# design.net
KiCad netlist of a schematic drawn in EasyEDA Pro
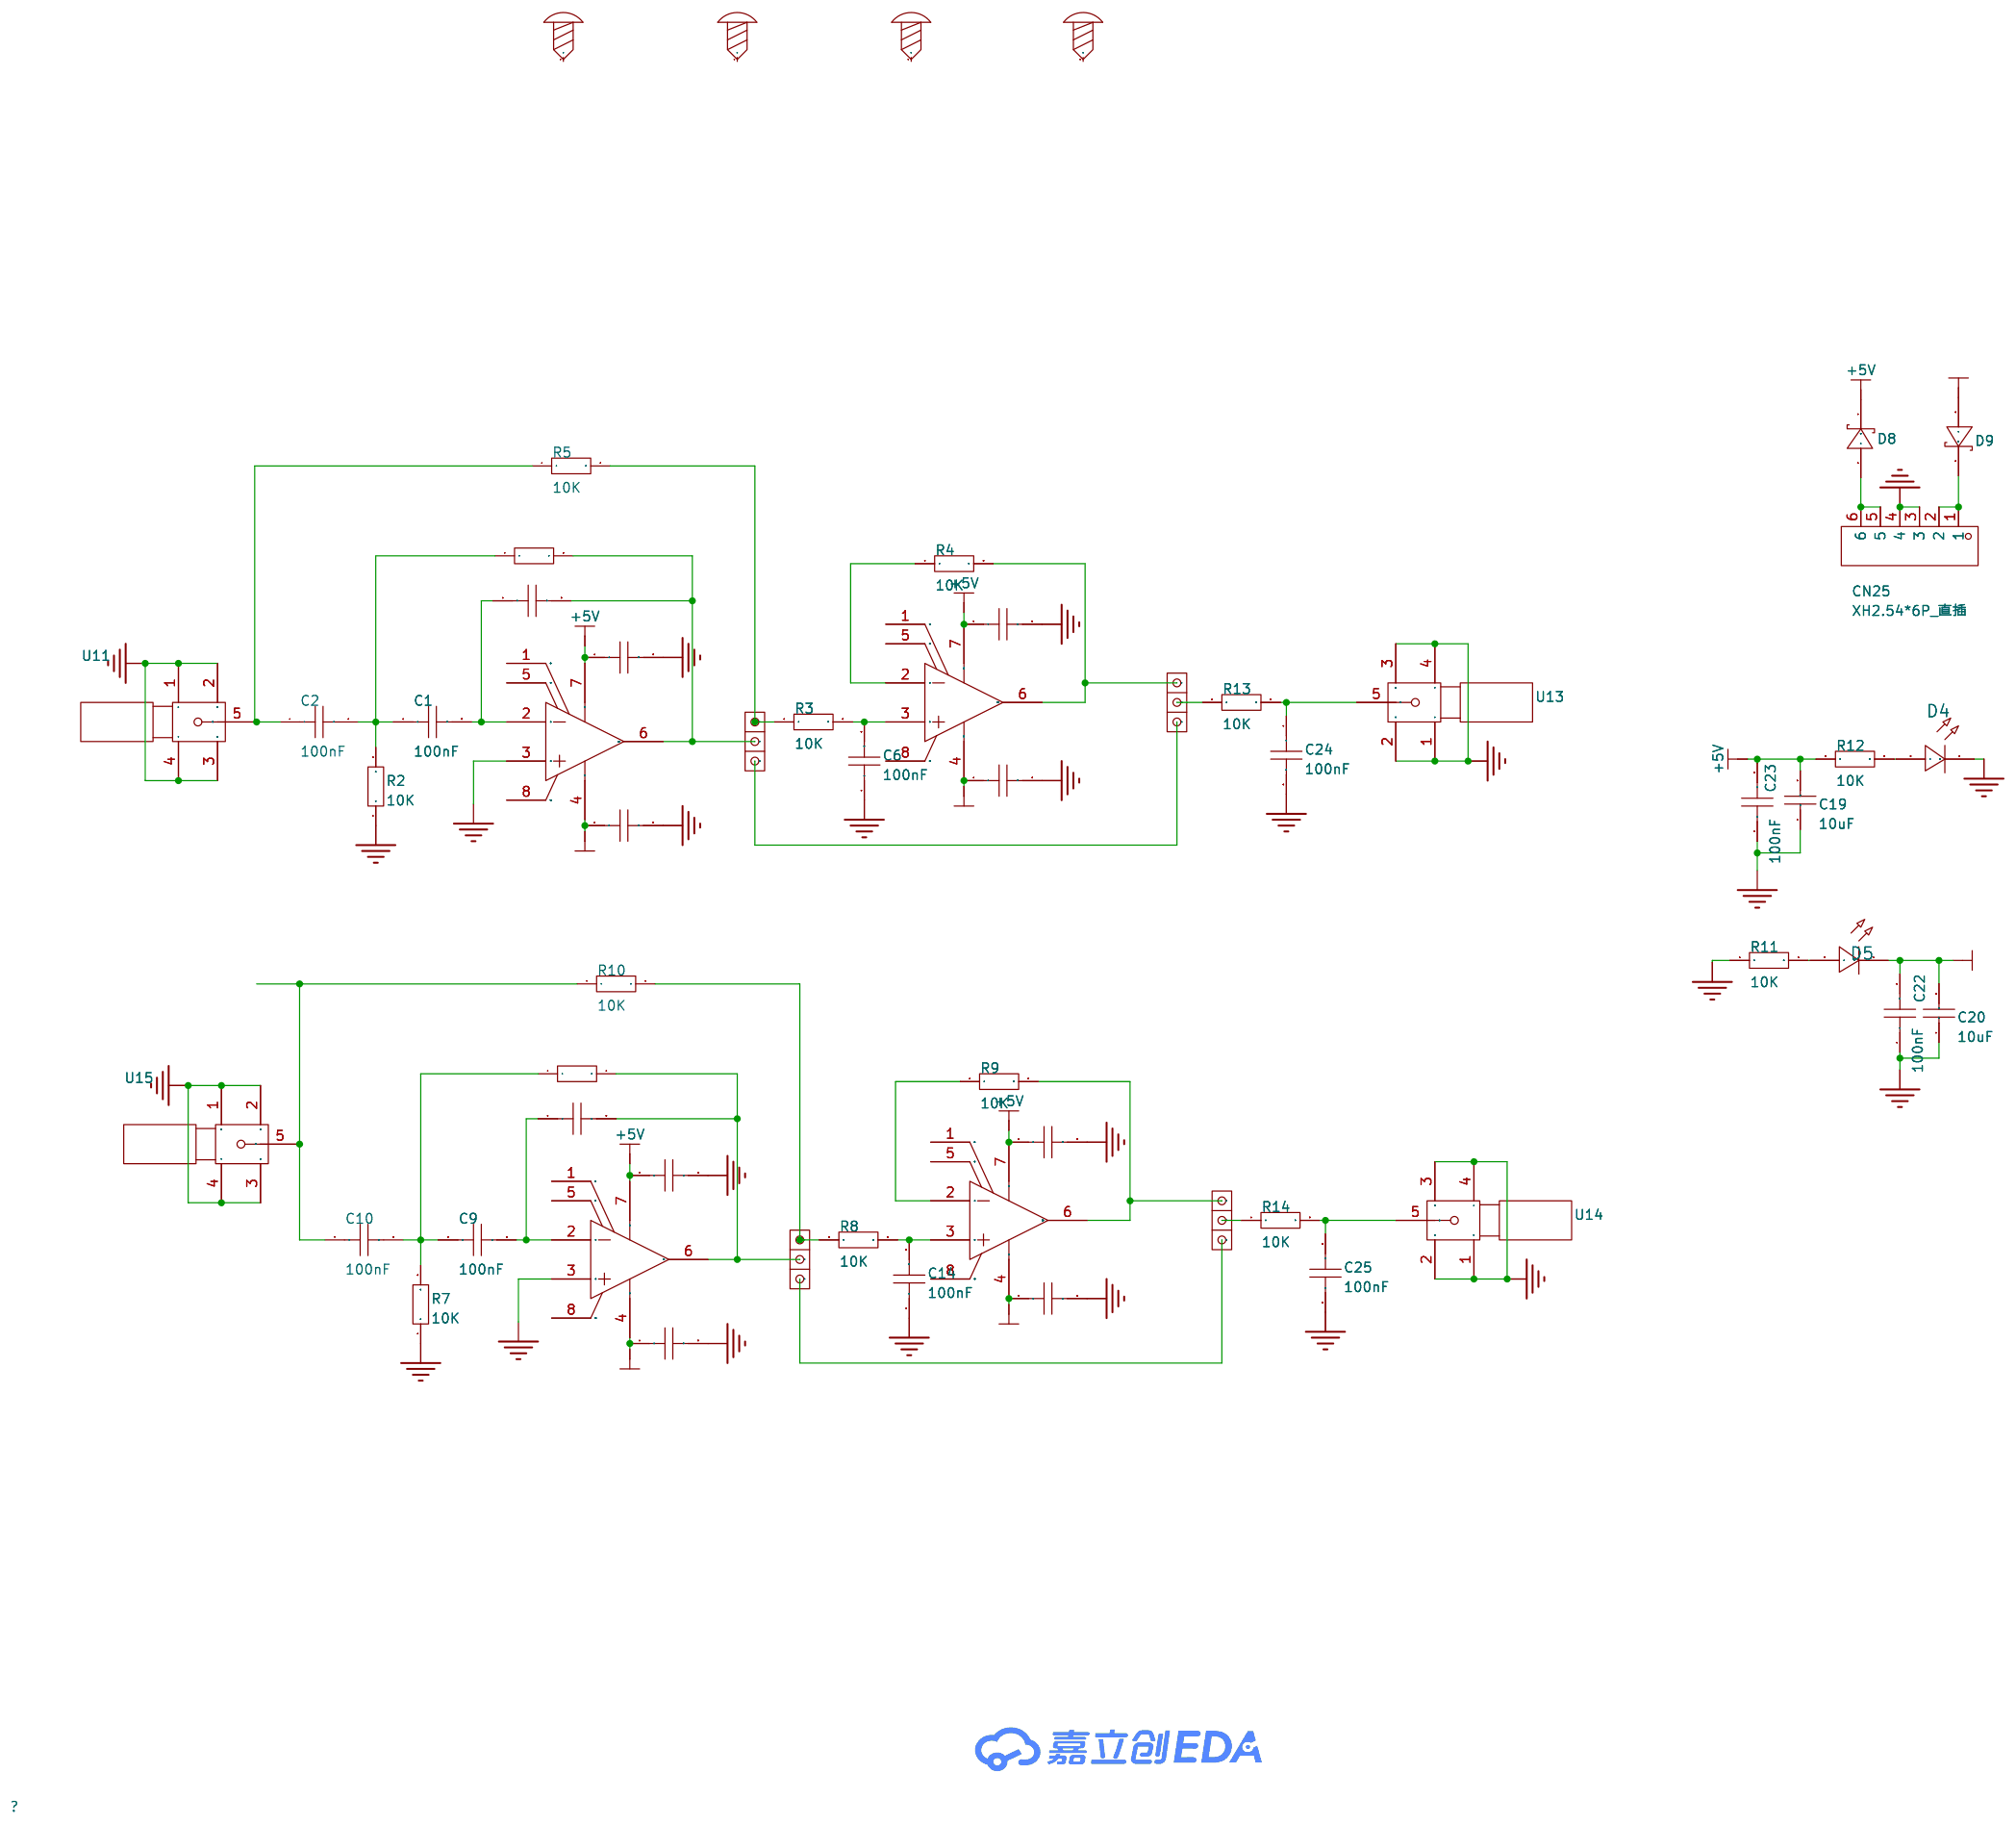
[diagram p0: schematic sheet]

(export (version "E")
  (design (tool "Eeschema 10.0.6"))
  (components
    (comp (ref "C1")
      (value "100nF")
      (footprint "easyedapro:C0805")
      (libsource (lib "easyedapro") (part "CapAcitance"))
    )
    (comp (ref "C2")
      (value "100nF")
      (footprint "easyedapro:C0805")
      (libsource (lib "easyedapro") (part "CapAcitance"))
    )
    (comp (ref "C3")
      (value "100nF")
      (footprint "easyedapro:C0805")
      (libsource (lib "easyedapro") (part "CapAcitance"))
    )
    (comp (ref "C4")
      (value "100nF")
      (footprint "easyedapro:C0805")
      (libsource (lib "easyedapro") (part "CapAcitance"))
    )
    (comp (ref "C5")
      (value "100nF")
      (footprint "easyedapro:C0805")
      (libsource (lib "easyedapro") (part "CapAcitance"))
    )
    (comp (ref "C6")
      (value "100nF")
      (footprint "easyedapro:C0805")
      (libsource (lib "easyedapro") (part "CapAcitance"))
    )
    (comp (ref "C7")
      (value "100nF")
      (footprint "easyedapro:C0805")
      (libsource (lib "easyedapro") (part "CapAcitance"))
    )
    (comp (ref "C8")
      (value "100nF")
      (footprint "easyedapro:C0805")
      (libsource (lib "easyedapro") (part "CapAcitance"))
    )
    (comp (ref "C9")
      (value "100nF")
      (footprint "easyedapro:C0805")
      (libsource (lib "easyedapro") (part "CapAcitance"))
    )
    (comp (ref "C10")
      (value "100nF")
      (footprint "easyedapro:C0805")
      (libsource (lib "easyedapro") (part "CapAcitance"))
    )
    (comp (ref "C11")
      (value "100nF")
      (footprint "easyedapro:C0805")
      (libsource (lib "easyedapro") (part "CapAcitance"))
    )
    (comp (ref "C12")
      (value "100nF")
      (footprint "easyedapro:C0805")
      (libsource (lib "easyedapro") (part "CapAcitance"))
    )
    (comp (ref "C13")
      (value "100nF")
      (footprint "easyedapro:C0805")
      (libsource (lib "easyedapro") (part "CapAcitance"))
    )
    (comp (ref "C14")
      (value "100nF")
      (footprint "easyedapro:C0805")
      (libsource (lib "easyedapro") (part "CapAcitance"))
    )
    (comp (ref "C15")
      (value "100nF")
      (footprint "easyedapro:C0805")
      (libsource (lib "easyedapro") (part "CapAcitance"))
    )
    (comp (ref "C16")
      (value "100nF")
      (footprint "easyedapro:C0805")
      (libsource (lib "easyedapro") (part "CapAcitance"))
    )
    (comp (ref "C19")
      (value "10uF")
      (footprint "easyedapro:C1210")
      (description "容值:10uF;精度:±10%;额定电压:25V;材质(温度系数):X7R;")
      (fields
        (field (name "Manufacturer Part") "CL32B106KAJNNNE")
        (field (name "Manufacturer") "SAMSUNG(三星)")
      )
      (libsource (lib "easyedapro") (part "CL32B106KAJNNNE"))
    )
    (comp (ref "C20")
      (value "10uF")
      (footprint "easyedapro:C1210")
      (description "容值:10uF;精度:±10%;额定电压:25V;材质(温度系数):X7R;")
      (fields
        (field (name "Manufacturer Part") "CL32B106KAJNNNE")
        (field (name "Manufacturer") "SAMSUNG(三星)")
      )
      (libsource (lib "easyedapro") (part "CL32B106KAJNNNE"))
    )
    (comp (ref "C22")
      (value "100nF")
      (footprint "easyedapro:C0805")
      (libsource (lib "easyedapro") (part "CapAcitance"))
    )
    (comp (ref "C23")
      (value "100nF")
      (footprint "easyedapro:C0805")
      (libsource (lib "easyedapro") (part "CapAcitance"))
    )
    (comp (ref "C24")
      (value "100nF")
      (footprint "easyedapro:C0805")
      (libsource (lib "easyedapro") (part "CapAcitance"))
    )
    (comp (ref "C25")
      (value "100nF")
      (footprint "easyedapro:C0805")
      (libsource (lib "easyedapro") (part "CapAcitance"))
    )
    (comp (ref "CN25")
      (value "XH2.54*6P_直插")
      (footprint "easyedapro:CONN-TH_XH2.54-6P")
      (libsource (lib "easyedapro") (part "XH2.54*6P_直插"))
    )
    (comp (ref "D4")
      (value "~")
      (footprint "easyedapro:LED_0805")
      (libsource (lib "easyedapro") (part "LED_R"))
    )
    (comp (ref "D5")
      (value "~")
      (footprint "easyedapro:LED_0805")
      (libsource (lib "easyedapro") (part "LED_R"))
    )
    (comp (ref "D8")
      (value "SD103AWS")
      (footprint "easyedapro:SOD-323_L1.8-W1.3-LS2.5-RD")
      (description "正向压降(Vf):600mV@200mA;直流反向耐压(Vr):40V;整流电流:350mA;")
      (fields (field (name "Manufacturer") "Hottech(合科泰)"))
      (libsource (lib "easyedapro") (part "SD103AWS_C181207"))
    )
    (comp (ref "D9")
      (value "SD103AWS")
      (footprint "easyedapro:SOD-323_L1.8-W1.3-LS2.5-RD")
      (description "正向压降(Vf):600mV@200mA;直流反向耐压(Vr):40V;整流电流:350mA;")
      (fields (field (name "Manufacturer") "Hottech(合科泰)"))
      (libsource (lib "easyedapro") (part "SD103AWS_C181207"))
    )
    (comp (ref "R1") (value "10K") (footprint "easyedapro:R0805") (libsource (lib "easyedapro") (part "电阻")))
    (comp (ref "R2") (value "10K") (footprint "easyedapro:R0805") (libsource (lib "easyedapro") (part "电阻")))
    (comp (ref "R3") (value "10K") (footprint "easyedapro:R0805") (libsource (lib "easyedapro") (part "电阻")))
    (comp (ref "R4") (value "10K") (footprint "easyedapro:R0805") (libsource (lib "easyedapro") (part "电阻")))
    (comp (ref "R5") (value "10K") (footprint "easyedapro:R0805") (libsource (lib "easyedapro") (part "电阻")))
    (comp (ref "R6") (value "10K") (footprint "easyedapro:R0805") (libsource (lib "easyedapro") (part "电阻")))
    (comp (ref "R7") (value "10K") (footprint "easyedapro:R0805") (libsource (lib "easyedapro") (part "电阻")))
    (comp (ref "R8") (value "10K") (footprint "easyedapro:R0805") (libsource (lib "easyedapro") (part "电阻")))
    (comp (ref "R9") (value "10K") (footprint "easyedapro:R0805") (libsource (lib "easyedapro") (part "电阻")))
    (comp (ref "R10") (value "10K") (footprint "easyedapro:R0805") (libsource (lib "easyedapro") (part "电阻")))
    (comp (ref "R11") (value "10K") (footprint "easyedapro:R0805") (libsource (lib "easyedapro") (part "电阻")))
    (comp (ref "R12") (value "10K") (footprint "easyedapro:R0805") (libsource (lib "easyedapro") (part "电阻")))
    (comp (ref "R13") (value "10K") (footprint "easyedapro:R0805") (libsource (lib "easyedapro") (part "电阻")))
    (comp (ref "R14") (value "10K") (footprint "easyedapro:R0805") (libsource (lib "easyedapro") (part "电阻")))
    (comp (ref "SCREW1")
      (value "~")
      (footprint "easyedapro:M3螺丝")
      (libsource (lib "easyedapro") (part "螺丝孔"))
    )
    (comp (ref "SCREW2")
      (value "~")
      (footprint "easyedapro:M3螺丝")
      (libsource (lib "easyedapro") (part "螺丝孔"))
    )
    (comp (ref "SCREW3")
      (value "~")
      (footprint "easyedapro:M3螺丝")
      (libsource (lib "easyedapro") (part "螺丝孔"))
    )
    (comp (ref "SCREW4")
      (value "~")
      (footprint "easyedapro:M3螺丝")
      (libsource (lib "easyedapro") (part "螺丝孔"))
    )
    (comp (ref "U1")
      (value "OPA695IDR")
      (footprint "easyedapro:SOIC-8_L5.0-W4.0-P1.27-LS6.1-BL")
      (description "放大器数:单路;增益带宽积(GBP):-;压摆率(SR):4.3V/ns;输入偏置电流(Ib):20uA;")
      (fields (field (name "Manufacturer") "TI(德州仪器)"))
      (libsource (lib "easyedapro") (part "OPA695IDR"))
    )
    (comp (ref "U2") (value "~") (footprint "easyedapro:1*3跳线") (libsource (lib "easyedapro") (part "1*3跳线")))
    (comp (ref "U3")
      (value "OPA695IDR")
      (footprint "easyedapro:SOIC-8_L5.0-W4.0-P1.27-LS6.1-BL")
      (description "放大器数:单路;增益带宽积(GBP):-;压摆率(SR):4.3V/ns;输入偏置电流(Ib):20uA;")
      (fields (field (name "Manufacturer") "TI(德州仪器)"))
      (libsource (lib "easyedapro") (part "OPA695IDR"))
    )
    (comp (ref "U4") (value "~") (footprint "easyedapro:1*3跳线") (libsource (lib "easyedapro") (part "1*3跳线")))
    (comp (ref "U5")
      (value "OPA695IDR")
      (footprint "easyedapro:SOIC-8_L5.0-W4.0-P1.27-LS6.1-BL")
      (description "放大器数:单路;增益带宽积(GBP):-;压摆率(SR):4.3V/ns;输入偏置电流(Ib):20uA;")
      (fields (field (name "Manufacturer") "TI(德州仪器)"))
      (libsource (lib "easyedapro") (part "OPA695IDR"))
    )
    (comp (ref "U6") (value "~") (footprint "easyedapro:1*3跳线") (libsource (lib "easyedapro") (part "1*3跳线")))
    (comp (ref "U7")
      (value "OPA695IDR")
      (footprint "easyedapro:SOIC-8_L5.0-W4.0-P1.27-LS6.1-BL")
      (description "放大器数:单路;增益带宽积(GBP):-;压摆率(SR):4.3V/ns;输入偏置电流(Ib):20uA;")
      (fields (field (name "Manufacturer") "TI(德州仪器)"))
      (libsource (lib "easyedapro") (part "OPA695IDR"))
    )
    (comp (ref "U8") (value "~") (footprint "easyedapro:1*3跳线") (libsource (lib "easyedapro") (part "1*3跳线")))
    (comp (ref "U11") (value "~") (footprint "easyedapro:SMA") (libsource (lib "easyedapro") (part "SMA")))
    (comp (ref "U13") (value "~") (footprint "easyedapro:SMA") (libsource (lib "easyedapro") (part "SMA")))
    (comp (ref "U14") (value "~") (footprint "easyedapro:SMA") (libsource (lib "easyedapro") (part "SMA")))
    (comp (ref "U15") (value "~") (footprint "easyedapro:SMA") (libsource (lib "easyedapro") (part "SMA")))
  )
  (nets
    (net (code "1") (name "+5V") (class "Default")
      (node (ref "C12") (pin "1") (pinfunction "1_1") (pintype "input"))
      (node (ref "C15") (pin "1") (pinfunction "1_1") (pintype "input"))
      (node (ref "C19") (pin "2") (pinfunction "2_2") (pintype "input"))
      (node (ref "C23") (pin "2") (pinfunction "2_2") (pintype "input"))
      (node (ref "C4") (pin "1") (pinfunction "1_1") (pintype "input"))
      (node (ref "C7") (pin "1") (pinfunction "1_1") (pintype "input"))
      (node (ref "D8") (pin "1") (pinfunction "C_1") (pintype "unspecified"))
      (node (ref "R12") (pin "1") (pinfunction "1_1") (pintype "input"))
      (node (ref "U1") (pin "7") (pinfunction "+VS_7") (pintype "unspecified"))
      (node (ref "U3") (pin "7") (pinfunction "+VS_7") (pintype "unspecified"))
      (node (ref "U5") (pin "7") (pinfunction "+VS_7") (pintype "unspecified"))
      (node (ref "U7") (pin "7") (pinfunction "+VS_7") (pintype "unspecified"))
    )
    (net (code "2") (name "-5V") (class "Default")
      (node (ref "C13") (pin "1") (pinfunction "1_1") (pintype "input"))
      (node (ref "C16") (pin "1") (pinfunction "1_1") (pintype "input"))
      (node (ref "C20") (pin "2") (pinfunction "2_2") (pintype "input"))
      (node (ref "C22") (pin "2") (pinfunction "2_2") (pintype "input"))
      (node (ref "C5") (pin "1") (pinfunction "1_1") (pintype "input"))
      (node (ref "C8") (pin "1") (pinfunction "1_1") (pintype "input"))
      (node (ref "D5") (pin "1") (pinfunction "C_1") (pintype "input"))
      (node (ref "D9") (pin "2") (pinfunction "A_2") (pintype "unspecified"))
      (node (ref "U1") (pin "4") (pinfunction "-VS_4") (pintype "unspecified"))
      (node (ref "U3") (pin "4") (pinfunction "-VS_4") (pintype "unspecified"))
      (node (ref "U5") (pin "4") (pinfunction "-VS_4") (pintype "unspecified"))
      (node (ref "U7") (pin "4") (pinfunction "-VS_4") (pintype "unspecified"))
    )
    (net (code "3") (name "GND") (class "Default")
      (node (ref "C12") (pin "2") (pinfunction "2_2") (pintype "input"))
      (node (ref "C13") (pin "2") (pinfunction "2_2") (pintype "input"))
      (node (ref "C14") (pin "1") (pinfunction "1_1") (pintype "input"))
      (node (ref "C15") (pin "2") (pinfunction "2_2") (pintype "input"))
      (node (ref "C16") (pin "2") (pinfunction "2_2") (pintype "input"))
      (node (ref "C19") (pin "1") (pinfunction "1_1") (pintype "input"))
      (node (ref "C20") (pin "1") (pinfunction "1_1") (pintype "input"))
      (node (ref "C22") (pin "1") (pinfunction "1_1") (pintype "input"))
      (node (ref "C23") (pin "1") (pinfunction "1_1") (pintype "input"))
      (node (ref "C24") (pin "2") (pinfunction "2_2") (pintype "input"))
      (node (ref "C25") (pin "2") (pinfunction "2_2") (pintype "input"))
      (node (ref "C4") (pin "2") (pinfunction "2_2") (pintype "input"))
      (node (ref "C5") (pin "2") (pinfunction "2_2") (pintype "input"))
      (node (ref "C6") (pin "1") (pinfunction "1_1") (pintype "input"))
      (node (ref "C7") (pin "2") (pinfunction "2_2") (pintype "input"))
      (node (ref "C8") (pin "2") (pinfunction "2_2") (pintype "input"))
      (node (ref "CN25") (pin "3") (pinfunction "3_3") (pintype "input"))
      (node (ref "CN25") (pin "4") (pinfunction "4_4") (pintype "input"))
      (node (ref "D4") (pin "1") (pinfunction "C_1") (pintype "input"))
      (node (ref "R11") (pin "1") (pinfunction "1_1") (pintype "input"))
      (node (ref "R2") (pin "1") (pinfunction "1_1") (pintype "input"))
      (node (ref "R7") (pin "1") (pinfunction "1_1") (pintype "input"))
      (node (ref "U1") (pin "3") (pinfunction "+IN_3") (pintype "unspecified"))
      (node (ref "U11") (pin "1") (pinfunction "1_1") (pintype "input"))
      (node (ref "U11") (pin "2") (pinfunction "2_2") (pintype "input"))
      (node (ref "U11") (pin "3") (pinfunction "3_3") (pintype "input"))
      (node (ref "U11") (pin "4") (pinfunction "4_4") (pintype "input"))
      (node (ref "U13") (pin "1") (pinfunction "1_1") (pintype "input"))
      (node (ref "U13") (pin "2") (pinfunction "2_2") (pintype "input"))
      (node (ref "U13") (pin "3") (pinfunction "3_3") (pintype "input"))
      (node (ref "U13") (pin "4") (pinfunction "4_4") (pintype "input"))
      (node (ref "U14") (pin "1") (pinfunction "1_1") (pintype "input"))
      (node (ref "U14") (pin "2") (pinfunction "2_2") (pintype "input"))
      (node (ref "U14") (pin "3") (pinfunction "3_3") (pintype "input"))
      (node (ref "U14") (pin "4") (pinfunction "4_4") (pintype "input"))
      (node (ref "U15") (pin "1") (pinfunction "1_1") (pintype "input"))
      (node (ref "U15") (pin "2") (pinfunction "2_2") (pintype "input"))
      (node (ref "U15") (pin "3") (pinfunction "3_3") (pintype "input"))
      (node (ref "U15") (pin "4") (pinfunction "4_4") (pintype "input"))
      (node (ref "U5") (pin "3") (pinfunction "+IN_3") (pintype "unspecified"))
    )
    (net (code "4") (name "Net-(C1-Pad1)") (class "Default")
      (node (ref "C1") (pin "1") (pinfunction "1_1") (pintype "input"))
      (node (ref "C2") (pin "2") (pinfunction "2_2") (pintype "input"))
      (node (ref "R1") (pin "1") (pinfunction "1_1") (pintype "input"))
      (node (ref "R2") (pin "2") (pinfunction "2_2") (pintype "input"))
    )
    (net (code "5") (name "Net-(C2-Pad1)") (class "Default")
      (node (ref "C2") (pin "1") (pinfunction "1_1") (pintype "input"))
      (node (ref "R5") (pin "1") (pinfunction "1_1") (pintype "input"))
      (node (ref "U11") (pin "5") (pinfunction "5_5") (pintype "input"))
    )
    (net (code "6") (name "Net-(C10-Pad1)") (class "Default")
      (node (ref "C10") (pin "1") (pinfunction "1_1") (pintype "input"))
      (node (ref "R10") (pin "1") (pinfunction "1_1") (pintype "input"))
      (node (ref "U15") (pin "5") (pinfunction "5_5") (pintype "input"))
    )
    (net (code "7") (name "Net-(C10-Pad2)") (class "Default")
      (node (ref "C10") (pin "2") (pinfunction "2_2") (pintype "input"))
      (node (ref "C9") (pin "1") (pinfunction "1_1") (pintype "input"))
      (node (ref "R6") (pin "1") (pinfunction "1_1") (pintype "input"))
      (node (ref "R7") (pin "2") (pinfunction "2_2") (pintype "input"))
    )
    (net (code "8") (name "Net-(C24-Pad1)") (class "Default")
      (node (ref "C24") (pin "1") (pinfunction "1_1") (pintype "input"))
      (node (ref "R13") (pin "2") (pinfunction "2_2") (pintype "input"))
      (node (ref "U13") (pin "5") (pinfunction "5_5") (pintype "input"))
    )
    (net (code "9") (name "Net-(C25-Pad1)") (class "Default")
      (node (ref "C25") (pin "1") (pinfunction "1_1") (pintype "input"))
      (node (ref "R14") (pin "2") (pinfunction "2_2") (pintype "input"))
      (node (ref "U14") (pin "5") (pinfunction "5_5") (pintype "input"))
    )
    (net (code "10") (name "Net-(D4-A)") (class "Default")
      (node (ref "D4") (pin "2") (pinfunction "A_2") (pintype "input"))
      (node (ref "R12") (pin "2") (pinfunction "2_2") (pintype "input"))
    )
    (net (code "11") (name "Net-(D5-A)") (class "Default")
      (node (ref "D5") (pin "2") (pinfunction "A_2") (pintype "input"))
      (node (ref "R11") (pin "2") (pinfunction "2_2") (pintype "input"))
    )
    (net (code "12") (name "Net-(D8-A)") (class "Default")
      (node (ref "CN25") (pin "5") (pinfunction "5_5") (pintype "input"))
      (node (ref "CN25") (pin "6") (pinfunction "6_6") (pintype "input"))
      (node (ref "D8") (pin "2") (pinfunction "A_2") (pintype "unspecified"))
    )
    (net (code "13") (name "Net-(D9-C)") (class "Default")
      (node (ref "CN25") (pin "1") (pinfunction "1_1") (pintype "input"))
      (node (ref "CN25") (pin "2") (pinfunction "2_2") (pintype "input"))
      (node (ref "D9") (pin "1") (pinfunction "C_1") (pintype "unspecified"))
    )
    (net (code "14") (name "Net-(R3-Pad1)") (class "Default")
      (node (ref "R3") (pin "1") (pinfunction "1_1") (pintype "input"))
      (node (ref "R5") (pin "2") (pinfunction "2_2") (pintype "input"))
      (node (ref "U2") (pin "1") (pinfunction "1_1") (pintype "input"))
    )
    (net (code "15") (name "Net-(R10-Pad2)") (class "Default")
      (node (ref "R10") (pin "2") (pinfunction "2_2") (pintype "input"))
      (node (ref "R8") (pin "1") (pinfunction "1_1") (pintype "input"))
      (node (ref "U6") (pin "1") (pinfunction "1_1") (pintype "input"))
    )
    (net (code "16") (name "Net-(R13-Pad1)") (class "Default")
      (node (ref "R13") (pin "1") (pinfunction "1_1") (pintype "input"))
      (node (ref "U4") (pin "2") (pinfunction "2_2") (pintype "input"))
    )
    (net (code "17") (name "Net-(R14-Pad1)") (class "Default")
      (node (ref "R14") (pin "1") (pinfunction "1_1") (pintype "input"))
      (node (ref "U8") (pin "2") (pinfunction "2_2") (pintype "input"))
    )
    (net (code "18") (name "Net-(U1--IN)") (class "Default")
      (node (ref "C1") (pin "2") (pinfunction "2_2") (pintype "input"))
      (node (ref "C3") (pin "1") (pinfunction "1_1") (pintype "input"))
      (node (ref "U1") (pin "2") (pinfunction "-IN_2") (pintype "unspecified"))
    )
    (net (code "19") (name "Net-(U1-Output)") (class "Default")
      (node (ref "C3") (pin "2") (pinfunction "2_2") (pintype "input"))
      (node (ref "R1") (pin "2") (pinfunction "2_2") (pintype "input"))
      (node (ref "U1") (pin "6") (pinfunction "Output_6") (pintype "output"))
      (node (ref "U2") (pin "2") (pinfunction "2_2") (pintype "input"))
    )
    (net (code "20") (name "Net-(U2-Pad3)") (class "Default")
      (node (ref "U2") (pin "3") (pinfunction "3_3") (pintype "input"))
      (node (ref "U4") (pin "3") (pinfunction "3_3") (pintype "input"))
    )
    (net (code "21") (name "Net-(U3-+IN)") (class "Default")
      (node (ref "C6") (pin "2") (pinfunction "2_2") (pintype "input"))
      (node (ref "R3") (pin "2") (pinfunction "2_2") (pintype "input"))
      (node (ref "U3") (pin "3") (pinfunction "+IN_3") (pintype "unspecified"))
    )
    (net (code "22") (name "Net-(U3--IN)") (class "Default")
      (node (ref "R4") (pin "1") (pinfunction "1_1") (pintype "input"))
      (node (ref "U3") (pin "2") (pinfunction "-IN_2") (pintype "unspecified"))
    )
    (net (code "23") (name "Net-(U3-Output)") (class "Default")
      (node (ref "R4") (pin "2") (pinfunction "2_2") (pintype "input"))
      (node (ref "U3") (pin "6") (pinfunction "Output_6") (pintype "output"))
      (node (ref "U4") (pin "1") (pinfunction "1_1") (pintype "input"))
    )
    (net (code "24") (name "Net-(U5--IN)") (class "Default")
      (node (ref "C11") (pin "1") (pinfunction "1_1") (pintype "input"))
      (node (ref "C9") (pin "2") (pinfunction "2_2") (pintype "input"))
      (node (ref "U5") (pin "2") (pinfunction "-IN_2") (pintype "unspecified"))
    )
    (net (code "25") (name "Net-(U5-Output)") (class "Default")
      (node (ref "C11") (pin "2") (pinfunction "2_2") (pintype "input"))
      (node (ref "R6") (pin "2") (pinfunction "2_2") (pintype "input"))
      (node (ref "U5") (pin "6") (pinfunction "Output_6") (pintype "output"))
      (node (ref "U6") (pin "2") (pinfunction "2_2") (pintype "input"))
    )
    (net (code "26") (name "Net-(U6-Pad3)") (class "Default")
      (node (ref "U6") (pin "3") (pinfunction "3_3") (pintype "input"))
      (node (ref "U8") (pin "3") (pinfunction "3_3") (pintype "input"))
    )
    (net (code "27") (name "Net-(U7-+IN)") (class "Default")
      (node (ref "C14") (pin "2") (pinfunction "2_2") (pintype "input"))
      (node (ref "R8") (pin "2") (pinfunction "2_2") (pintype "input"))
      (node (ref "U7") (pin "3") (pinfunction "+IN_3") (pintype "unspecified"))
    )
    (net (code "28") (name "Net-(U7--IN)") (class "Default")
      (node (ref "R9") (pin "1") (pinfunction "1_1") (pintype "input"))
      (node (ref "U7") (pin "2") (pinfunction "-IN_2") (pintype "unspecified"))
    )
    (net (code "29") (name "Net-(U7-Output)") (class "Default")
      (node (ref "R9") (pin "2") (pinfunction "2_2") (pintype "input"))
      (node (ref "U7") (pin "6") (pinfunction "Output_6") (pintype "output"))
      (node (ref "U8") (pin "1") (pinfunction "1_1") (pintype "input"))
    )
    (net (code "30") (name "unconnected-(SCREW1-Pad1)") (class "Default")
      (node (ref "SCREW1") (pin "1") (pinfunction "1_1") (pintype "input"))
    )
    (net (code "31") (name "unconnected-(SCREW2-Pad1)") (class "Default")
      (node (ref "SCREW2") (pin "1") (pinfunction "1_1") (pintype "input"))
    )
    (net (code "32") (name "unconnected-(SCREW3-Pad1)") (class "Default")
      (node (ref "SCREW3") (pin "1") (pinfunction "1_1") (pintype "input"))
    )
    (net (code "33") (name "unconnected-(SCREW4-Pad1)") (class "Default")
      (node (ref "SCREW4") (pin "1") (pinfunction "1_1") (pintype "input"))
    )
    (net (code "34") (name "unconnected-(U1-DIS#-Pad8)") (class "Default")
      (node (ref "U1") (pin "8") (pinfunction "DIS#_8") (pintype "unspecified"))
    )
    (net (code "35") (name "unconnected-(U1-NC-Pad1)") (class "Default")
      (node (ref "U1") (pin "1") (pinfunction "NC_1") (pintype "unspecified"))
    )
    (net (code "36") (name "unconnected-(U1-NC-Pad5)") (class "Default")
      (node (ref "U1") (pin "5") (pinfunction "NC_5") (pintype "unspecified"))
    )
    (net (code "37") (name "unconnected-(U3-DIS#-Pad8)") (class "Default")
      (node (ref "U3") (pin "8") (pinfunction "DIS#_8") (pintype "unspecified"))
    )
    (net (code "38") (name "unconnected-(U3-NC-Pad1)") (class "Default")
      (node (ref "U3") (pin "1") (pinfunction "NC_1") (pintype "unspecified"))
    )
    (net (code "39") (name "unconnected-(U3-NC-Pad5)") (class "Default")
      (node (ref "U3") (pin "5") (pinfunction "NC_5") (pintype "unspecified"))
    )
    (net (code "40") (name "unconnected-(U5-DIS#-Pad8)") (class "Default")
      (node (ref "U5") (pin "8") (pinfunction "DIS#_8") (pintype "unspecified"))
    )
    (net (code "41") (name "unconnected-(U5-NC-Pad1)") (class "Default")
      (node (ref "U5") (pin "1") (pinfunction "NC_1") (pintype "unspecified"))
    )
    (net (code "42") (name "unconnected-(U5-NC-Pad5)") (class "Default")
      (node (ref "U5") (pin "5") (pinfunction "NC_5") (pintype "unspecified"))
    )
    (net (code "43") (name "unconnected-(U7-DIS#-Pad8)") (class "Default")
      (node (ref "U7") (pin "8") (pinfunction "DIS#_8") (pintype "unspecified"))
    )
    (net (code "44") (name "unconnected-(U7-NC-Pad1)") (class "Default")
      (node (ref "U7") (pin "1") (pinfunction "NC_1") (pintype "unspecified"))
    )
    (net (code "45") (name "unconnected-(U7-NC-Pad5)") (class "Default")
      (node (ref "U7") (pin "5") (pinfunction "NC_5") (pintype "unspecified"))
    )
  )
)
